# 140314_AriloTX_REV2_0_0.net
KiCad netlist of a schematic drawn in EAGLE
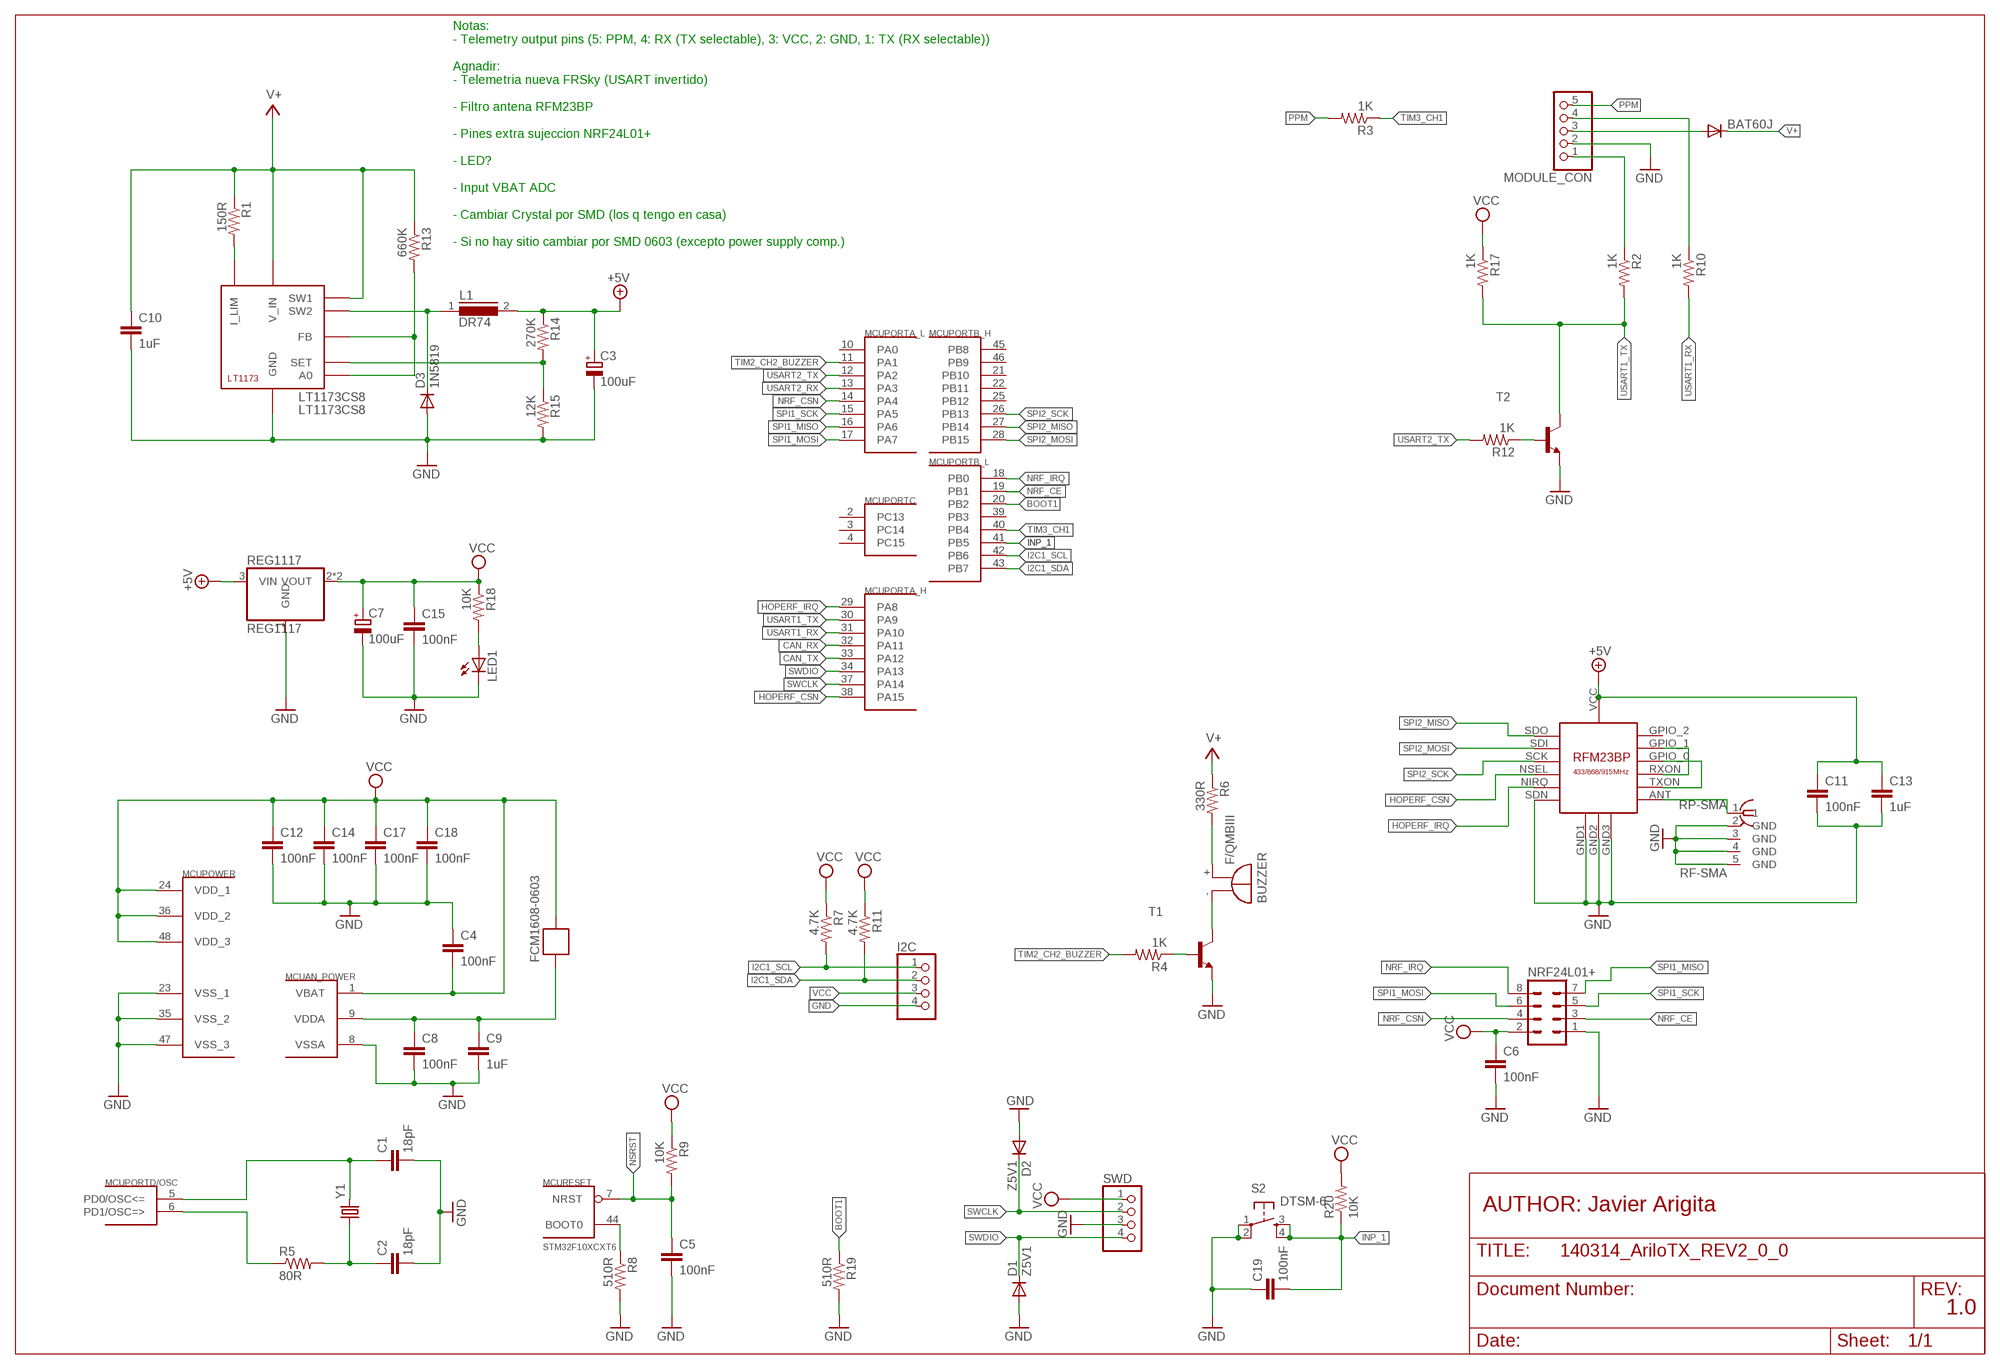
[diagram p0: schematic, sheet 1]

(export (version "E")
  (design (tool "Eeschema 10.0.6"))
  (components
    (comp (ref "BAT60J")
      (value "DIODE-SOD323-R")
      (footprint "eagle-import:SOD323-R")
      (libsource (lib "eagle-import") (part "DIODE-SOD323-R"))
    )
    (comp (ref "BUZZER")
      (value "F/QMBIII")
      (footprint "eagle-import:F_QMBIII")
      (libsource (lib "eagle-import") (part "F/QMBIII"))
    )
    (comp (ref "C1")
      (value "18pF")
      (footprint "eagle-import:C0805")
      (libsource (lib "eagle-import") (part "C-EUC0805"))
    )
    (comp (ref "C2")
      (value "18pF")
      (footprint "eagle-import:C0805")
      (libsource (lib "eagle-import") (part "C-EUC0805"))
    )
    (comp (ref "C3")
      (value "100uF")
      (footprint "eagle-import:SMC_B")
      (libsource (lib "eagle-import") (part "CPOL-EUSMCB"))
    )
    (comp (ref "C4")
      (value "100nF")
      (footprint "eagle-import:C0805")
      (libsource (lib "eagle-import") (part "C-EUC0805"))
    )
    (comp (ref "C5")
      (value "100nF")
      (footprint "eagle-import:C0805")
      (libsource (lib "eagle-import") (part "C-EUC0805"))
    )
    (comp (ref "C6")
      (value "100nF")
      (footprint "eagle-import:C0805")
      (libsource (lib "eagle-import") (part "C-EUC0805"))
    )
    (comp (ref "C7")
      (value "100uF")
      (footprint "eagle-import:SMC_B")
      (libsource (lib "eagle-import") (part "CPOL-EUSMCB"))
    )
    (comp (ref "C8")
      (value "100nF")
      (footprint "eagle-import:C0805")
      (libsource (lib "eagle-import") (part "C-EUC0805"))
    )
    (comp (ref "C9")
      (value "1uF")
      (footprint "eagle-import:C3216")
      (libsource (lib "eagle-import") (part "resistor_C-EUC3216"))
    )
    (comp (ref "C10")
      (value "1uF")
      (footprint "eagle-import:C3216")
      (libsource (lib "eagle-import") (part "resistor_C-EUC3216"))
    )
    (comp (ref "C11")
      (value "100nF")
      (footprint "eagle-import:C0805")
      (libsource (lib "eagle-import") (part "C-EUC0805"))
    )
    (comp (ref "C12")
      (value "100nF")
      (footprint "eagle-import:C0805")
      (libsource (lib "eagle-import") (part "C-EUC0805"))
    )
    (comp (ref "C13")
      (value "1uF")
      (footprint "eagle-import:C3216")
      (libsource (lib "eagle-import") (part "resistor_C-EUC3216"))
    )
    (comp (ref "C14")
      (value "100nF")
      (footprint "eagle-import:C0805")
      (libsource (lib "eagle-import") (part "C-EUC0805"))
    )
    (comp (ref "C15")
      (value "100nF")
      (footprint "eagle-import:C0805")
      (libsource (lib "eagle-import") (part "C-EUC0805"))
    )
    (comp (ref "C17")
      (value "100nF")
      (footprint "eagle-import:C0805")
      (libsource (lib "eagle-import") (part "C-EUC0805"))
    )
    (comp (ref "C18")
      (value "100nF")
      (footprint "eagle-import:C0805")
      (libsource (lib "eagle-import") (part "C-EUC0805"))
    )
    (comp (ref "C19")
      (value "100nF")
      (footprint "eagle-import:C0805")
      (libsource (lib "eagle-import") (part "C-EUC0805"))
    )
    (comp (ref "D1")
      (value "Z5V1")
      (footprint "eagle-import:SOD323-R")
      (libsource (lib "eagle-import") (part "DIODE-SOD323-R"))
    )
    (comp (ref "D2")
      (value "Z5V1")
      (footprint "eagle-import:SOD323-R")
      (libsource (lib "eagle-import") (part "DIODE-SOD323-R"))
    )
    (comp (ref "D3")
      (value "1N5819")
      (footprint "eagle-import:DO214AC")
      (libsource (lib "eagle-import") (part "DIODE-DO214AC"))
    )
    (comp (ref "FCM1608-0603")
      (value "FERRITE-BEAD")
      (footprint "eagle-import:R0603")
      (libsource (lib "eagle-import") (part "FERRITE-BEAD"))
    )
    (comp (ref "I2C")
      (value "PINHD-1X4")
      (footprint "eagle-import:1X04")
      (libsource (lib "eagle-import") (part "PINHD-1X4"))
    )
    (comp (ref "L1")
      (value "DR74")
      (footprint "eagle-import:DR74")
      (libsource (lib "eagle-import") (part "DR74"))
    )
    (comp (ref "LED1")
      (value "LED0805")
      (footprint "eagle-import:CHIPLED_0805")
      (libsource (lib "eagle-import") (part "LED0805"))
    )
    (comp (ref "LT1173CS8")
      (value "LT1173CS8")
      (footprint "eagle-import:SOIC8")
      (libsource (lib "eagle-import") (part "LT1173CS8"))
    )
    (comp (ref "MCU")
      (value "STM32F10XCXT6")
      (footprint "eagle-import:TQFP48")
      (libsource (lib "eagle-import") (part "STM32F10XCXT6"))
    )
    (comp (ref "MODULE_CON")
      (value "PINHD-1X5")
      (footprint "eagle-import:1X05")
      (libsource (lib "eagle-import") (part "PINHD-1X5"))
    )
    (comp (ref "NRF24L01+")
      (value "MA04-2")
      (footprint "eagle-import:MA04-2")
      (libsource (lib "eagle-import") (part "MA04-2"))
    )
    (comp (ref "R1")
      (value "150R")
      (footprint "eagle-import:R0805")
      (libsource (lib "eagle-import") (part "RESISTOR0805"))
    )
    (comp (ref "R2")
      (value "1K")
      (footprint "eagle-import:R0805")
      (libsource (lib "eagle-import") (part "RESISTOR0805"))
    )
    (comp (ref "R3")
      (value "1K")
      (footprint "eagle-import:R0805")
      (libsource (lib "eagle-import") (part "RESISTOR0805"))
    )
    (comp (ref "R4")
      (value "1K")
      (footprint "eagle-import:R0805")
      (libsource (lib "eagle-import") (part "RESISTOR0805"))
    )
    (comp (ref "R5")
      (value "80R")
      (footprint "eagle-import:R0805")
      (libsource (lib "eagle-import") (part "RESISTOR0805"))
    )
    (comp (ref "R6")
      (value "330R")
      (footprint "eagle-import:R0805")
      (libsource (lib "eagle-import") (part "RESISTOR0805"))
    )
    (comp (ref "R7")
      (value "4.7K")
      (footprint "eagle-import:R0805")
      (libsource (lib "eagle-import") (part "RESISTOR0805"))
    )
    (comp (ref "R8")
      (value "510R")
      (footprint "eagle-import:R0805")
      (libsource (lib "eagle-import") (part "RESISTOR0805"))
    )
    (comp (ref "R9")
      (value "10K")
      (footprint "eagle-import:R0805")
      (libsource (lib "eagle-import") (part "RESISTOR0805"))
    )
    (comp (ref "R10")
      (value "1K")
      (footprint "eagle-import:R0805")
      (libsource (lib "eagle-import") (part "RESISTOR0805"))
    )
    (comp (ref "R11")
      (value "4.7K")
      (footprint "eagle-import:R0805")
      (libsource (lib "eagle-import") (part "RESISTOR0805"))
    )
    (comp (ref "R12")
      (value "1K")
      (footprint "eagle-import:R0805")
      (libsource (lib "eagle-import") (part "RESISTOR0805"))
    )
    (comp (ref "R13")
      (value "660K")
      (footprint "eagle-import:R0805")
      (libsource (lib "eagle-import") (part "RESISTOR0805"))
    )
    (comp (ref "R14")
      (value "270K")
      (footprint "eagle-import:R0805")
      (libsource (lib "eagle-import") (part "RESISTOR0805"))
    )
    (comp (ref "R15")
      (value "12K")
      (footprint "eagle-import:R0805")
      (libsource (lib "eagle-import") (part "RESISTOR0805"))
    )
    (comp (ref "R17")
      (value "1K")
      (footprint "eagle-import:R0805")
      (libsource (lib "eagle-import") (part "RESISTOR0805"))
    )
    (comp (ref "R18")
      (value "10K")
      (footprint "eagle-import:R0805")
      (libsource (lib "eagle-import") (part "RESISTOR0805"))
    )
    (comp (ref "R19")
      (value "510R")
      (footprint "eagle-import:R0805")
      (libsource (lib "eagle-import") (part "RESISTOR0805"))
    )
    (comp (ref "R20")
      (value "10K")
      (footprint "eagle-import:R0805")
      (libsource (lib "eagle-import") (part "RESISTOR0805"))
    )
    (comp (ref "REG1117")
      (value "REG1117")
      (footprint "eagle-import:SOT223")
      (libsource (lib "eagle-import") (part "REG1117"))
    )
    (comp (ref "RP-SMA")
      (value "RF-SMA")
      (footprint "eagle-import:BU-SMA-H")
      (libsource (lib "eagle-import") (part "RF-SMA"))
    )
    (comp (ref "S2")
      (value "DTSM-6")
      (footprint "eagle-import:DTSM-6")
      (libsource (lib "eagle-import") (part "DTSM-6"))
    )
    (comp (ref "SWD")
      (value "PINHD-1X4")
      (footprint "eagle-import:1X04")
      (libsource (lib "eagle-import") (part "PINHD-1X4"))
    )
    (comp (ref "T1")
      (value "BC848-NPN-SOT23-BEC")
      (footprint "eagle-import:SOT23-BEC")
      (libsource (lib "eagle-import") (part "-NPN-SOT23-BECBC848"))
    )
    (comp (ref "T2")
      (value "BC848-NPN-SOT23-BEC")
      (footprint "eagle-import:SOT23-BEC")
      (libsource (lib "eagle-import") (part "-NPN-SOT23-BECBC848"))
    )
    (comp (ref "U$1")
      (value "RFM23BP")
      (footprint "eagle-import:RFM23BP")
      (libsource (lib "eagle-import") (part "RFM23BP"))
    )
    (comp (ref "Y1")
      (value "CRYSTAL5X3")
      (footprint "eagle-import:CRYSTAL-SMD-5X3")
      (libsource (lib "eagle-import") (part "CRYSTAL5X3"))
    )
  )
  (nets
    (net (code "1") (name "+5V") (class "Default")
      (node (ref "C11") (pin "1") (pinfunction "1_1") (pintype "passive"))
      (node (ref "C13") (pin "1") (pinfunction "1_1") (pintype "passive"))
      (node (ref "C3") (pin "+") (pinfunction "+_+") (pintype "passive"))
      (node (ref "L1") (pin "2") (pinfunction "2_2") (pintype "passive"))
      (node (ref "R14") (pin "1") (pinfunction "1_1") (pintype "passive"))
      (node (ref "REG1117") (pin "3") (pinfunction "VIN_3") (pintype "input"))
      (node (ref "U$1") (pin "VCC") (pinfunction "VCC_VCC") (pintype "power_in"))
    )
    (net (code "2") (name "BOOT1") (class "Default")
      (node (ref "MCU") (pin "20") (pinfunction "PB2_20") (pintype "bidirectional"))
      (node (ref "R19") (pin "1") (pinfunction "1_1") (pintype "passive"))
    )
    (net (code "3") (name "CAN_RX") (class "Default")
      (node (ref "MCU") (pin "32") (pinfunction "PA11_32") (pintype "bidirectional"))
    )
    (net (code "4") (name "CAN_TX") (class "Default")
      (node (ref "MCU") (pin "33") (pinfunction "PA12_33") (pintype "bidirectional"))
    )
    (net (code "5") (name "GND") (class "Default")
      (node (ref "C1") (pin "2") (pinfunction "2_2") (pintype "passive"))
      (node (ref "C10") (pin "2") (pinfunction "2_2") (pintype "passive"))
      (node (ref "C11") (pin "2") (pinfunction "2_2") (pintype "passive"))
      (node (ref "C12") (pin "2") (pinfunction "2_2") (pintype "passive"))
      (node (ref "C13") (pin "2") (pinfunction "2_2") (pintype "passive"))
      (node (ref "C14") (pin "2") (pinfunction "2_2") (pintype "passive"))
      (node (ref "C15") (pin "2") (pinfunction "2_2") (pintype "passive"))
      (node (ref "C17") (pin "2") (pinfunction "2_2") (pintype "passive"))
      (node (ref "C18") (pin "2") (pinfunction "2_2") (pintype "passive"))
      (node (ref "C19") (pin "1") (pinfunction "1_1") (pintype "passive"))
      (node (ref "C2") (pin "2") (pinfunction "2_2") (pintype "passive"))
      (node (ref "C3") (pin "-") (pinfunction "-_-") (pintype "passive"))
      (node (ref "C4") (pin "1") (pinfunction "1_1") (pintype "passive"))
      (node (ref "C5") (pin "2") (pinfunction "2_2") (pintype "passive"))
      (node (ref "C6") (pin "2") (pinfunction "2_2") (pintype "passive"))
      (node (ref "C7") (pin "-") (pinfunction "-_-") (pintype "passive"))
      (node (ref "C8") (pin "2") (pinfunction "2_2") (pintype "passive"))
      (node (ref "C9") (pin "2") (pinfunction "2_2") (pintype "passive"))
      (node (ref "D1") (pin "A") (pinfunction "A_A") (pintype "passive"))
      (node (ref "D2") (pin "A") (pinfunction "A_A") (pintype "passive"))
      (node (ref "D3") (pin "A") (pinfunction "A_A") (pintype "passive"))
      (node (ref "I2C") (pin "4") (pinfunction "4_4") (pintype "passive"))
      (node (ref "LED1") (pin "C") (pinfunction "C_C") (pintype "passive"))
      (node (ref "LT1173CS8") (pin "5") (pinfunction "GND_5") (pintype "power_in"))
      (node (ref "MCU") (pin "23") (pinfunction "VSS_1_23") (pintype "power_in"))
      (node (ref "MCU") (pin "35") (pinfunction "VSS_2_35") (pintype "power_in"))
      (node (ref "MCU") (pin "47") (pinfunction "VSS_3_47") (pintype "power_in"))
      (node (ref "MCU") (pin "8") (pinfunction "VSSA_8") (pintype "power_in"))
      (node (ref "MODULE_CON") (pin "2") (pinfunction "2_2") (pintype "passive"))
      (node (ref "NRF24L01+") (pin "1") (pinfunction "1_1") (pintype "passive"))
      (node (ref "R15") (pin "2") (pinfunction "2_2") (pintype "passive"))
      (node (ref "R19") (pin "2") (pinfunction "2_2") (pintype "passive"))
      (node (ref "R8") (pin "2") (pinfunction "2_2") (pintype "passive"))
      (node (ref "REG1117") (pin "1") (pinfunction "GND_1") (pintype "power_in"))
      (node (ref "RP-SMA") (pin "2") (pinfunction "GND_2") (pintype "power_in"))
      (node (ref "RP-SMA") (pin "3") (pinfunction "GND_3") (pintype "bidirectional"))
      (node (ref "RP-SMA") (pin "4") (pinfunction "GND_4") (pintype "bidirectional"))
      (node (ref "RP-SMA") (pin "5") (pinfunction "GND_5") (pintype "bidirectional"))
      (node (ref "S2") (pin "1") (pinfunction "1_1") (pintype "passive"))
      (node (ref "S2") (pin "2") (pinfunction "2_2") (pintype "passive"))
      (node (ref "SWD") (pin "3") (pinfunction "3_3") (pintype "passive"))
      (node (ref "T1") (pin "E") (pinfunction "E_E") (pintype "passive"))
      (node (ref "T2") (pin "E") (pinfunction "E_E") (pintype "passive"))
      (node (ref "U$1") (pin "GND1") (pinfunction "GND1_GND1") (pintype "power_in"))
      (node (ref "U$1") (pin "GND2") (pinfunction "GND2_GND2") (pintype "power_in"))
      (node (ref "U$1") (pin "GND3") (pinfunction "GND3_GND3") (pintype "power_in"))
      (node (ref "U$1") (pin "SDN") (pinfunction "SDN_SDN") (pintype "bidirectional"))
    )
    (net (code "6") (name "HOPERF_CSN") (class "Default")
      (node (ref "MCU") (pin "38") (pinfunction "PA15_38") (pintype "bidirectional"))
      (node (ref "U$1") (pin "NSEL") (pinfunction "NSEL_NSEL") (pintype "bidirectional"))
    )
    (net (code "7") (name "HOPERF_IRQ") (class "Default")
      (node (ref "MCU") (pin "29") (pinfunction "PA8_29") (pintype "bidirectional"))
      (node (ref "U$1") (pin "NIRQ") (pinfunction "NIRQ_NIRQ") (pintype "bidirectional"))
    )
    (net (code "8") (name "I2C1_SCL") (class "Default")
      (node (ref "I2C") (pin "1") (pinfunction "1_1") (pintype "passive"))
      (node (ref "MCU") (pin "42") (pinfunction "PB6_42") (pintype "bidirectional"))
      (node (ref "R7") (pin "2") (pinfunction "2_2") (pintype "passive"))
    )
    (net (code "9") (name "I2C1_SDA") (class "Default")
      (node (ref "I2C") (pin "2") (pinfunction "2_2") (pintype "passive"))
      (node (ref "MCU") (pin "43") (pinfunction "PB7_43") (pintype "bidirectional"))
      (node (ref "R11") (pin "2") (pinfunction "2_2") (pintype "passive"))
    )
    (net (code "10") (name "INP_1") (class "Default")
      (node (ref "C19") (pin "2") (pinfunction "2_2") (pintype "passive"))
      (node (ref "MCU") (pin "41") (pinfunction "PB5_41") (pintype "bidirectional"))
      (node (ref "R20") (pin "1") (pinfunction "1_1") (pintype "passive"))
      (node (ref "S2") (pin "3") (pinfunction "3_3") (pintype "passive"))
      (node (ref "S2") (pin "4") (pinfunction "4_4") (pintype "passive"))
    )
    (net (code "11") (name "NRF_CE") (class "Default")
      (node (ref "MCU") (pin "19") (pinfunction "PB1_19") (pintype "bidirectional"))
      (node (ref "NRF24L01+") (pin "3") (pinfunction "3_3") (pintype "passive"))
    )
    (net (code "12") (name "NRF_CSN") (class "Default")
      (node (ref "MCU") (pin "14") (pinfunction "PA4_14") (pintype "bidirectional"))
      (node (ref "NRF24L01+") (pin "4") (pinfunction "4_4") (pintype "passive"))
    )
    (net (code "13") (name "NRF_IRQ") (class "Default")
      (node (ref "MCU") (pin "18") (pinfunction "PB0_18") (pintype "bidirectional"))
      (node (ref "NRF24L01+") (pin "8") (pinfunction "8_8") (pintype "passive"))
    )
    (net (code "14") (name "NSRST") (class "Default")
      (node (ref "C5") (pin "1") (pinfunction "1_1") (pintype "passive"))
      (node (ref "MCU") (pin "7") (pinfunction "NRST_7") (pintype "input"))
      (node (ref "R9") (pin "2") (pinfunction "2_2") (pintype "passive"))
    )
    (net (code "15") (name "Net-(BAT60J-PadA)") (class "Default")
      (node (ref "BAT60J") (pin "A") (pinfunction "A_A") (pintype "passive"))
      (node (ref "MODULE_CON") (pin "3") (pinfunction "3_3") (pintype "passive"))
    )
    (net (code "16") (name "Net-(BUZZER-+)") (class "Default")
      (node (ref "BUZZER") (pin "-") (pinfunction "+_-") (pintype "passive"))
      (node (ref "T1") (pin "C") (pinfunction "C_C") (pintype "passive"))
    )
    (net (code "17") (name "Net-(BUZZER--)") (class "Default")
      (node (ref "BUZZER") (pin "+") (pinfunction "-_+") (pintype "passive"))
      (node (ref "R6") (pin "2") (pinfunction "2_2") (pintype "passive"))
    )
    (net (code "18") (name "Net-(C2-Pad1)") (class "Default")
      (node (ref "C2") (pin "1") (pinfunction "1_1") (pintype "passive"))
      (node (ref "R5") (pin "2") (pinfunction "2_2") (pintype "passive"))
      (node (ref "Y1") (pin "1") (pinfunction "1_1") (pintype "passive"))
    )
    (net (code "19") (name "Net-(FCM1608-0603-P$2)") (class "Default")
      (node (ref "C8") (pin "1") (pinfunction "1_1") (pintype "passive"))
      (node (ref "C9") (pin "1") (pinfunction "1_1") (pintype "passive"))
      (node (ref "FCM1608-0603") (pin "2") (pinfunction "P$2_2") (pintype "bidirectional"))
      (node (ref "MCU") (pin "9") (pinfunction "VDDA_9") (pintype "power_in"))
    )
    (net (code "20") (name "Net-(LED1-PadA)") (class "Default")
      (node (ref "LED1") (pin "A") (pinfunction "A_A") (pintype "passive"))
      (node (ref "R18") (pin "2") (pinfunction "2_2") (pintype "passive"))
    )
    (net (code "21") (name "Net-(LT1173CS8-A0)") (class "Default")
      (node (ref "LT1173CS8") (pin "6") (pinfunction "A0_6") (pintype "passive"))
      (node (ref "LT1173CS8") (pin "8") (pinfunction "FB_8") (pintype "passive"))
      (node (ref "R13") (pin "2") (pinfunction "2_2") (pintype "passive"))
    )
    (net (code "22") (name "Net-(LT1173CS8-I_LIM)") (class "Default")
      (node (ref "LT1173CS8") (pin "1") (pinfunction "I_LIM_1") (pintype "passive"))
      (node (ref "R1") (pin "2") (pinfunction "2_2") (pintype "passive"))
    )
    (net (code "23") (name "Net-(LT1173CS8-SET)") (class "Default")
      (node (ref "LT1173CS8") (pin "7") (pinfunction "SET_7") (pintype "passive"))
      (node (ref "R14") (pin "2") (pinfunction "2_2") (pintype "passive"))
      (node (ref "R15") (pin "1") (pinfunction "1_1") (pintype "passive"))
    )
    (net (code "24") (name "Net-(LT1173CS8-SW2)") (class "Default")
      (node (ref "D3") (pin "C") (pinfunction "C_C") (pintype "passive"))
      (node (ref "L1") (pin "1") (pinfunction "1_1") (pintype "passive"))
      (node (ref "LT1173CS8") (pin "4") (pinfunction "SW2_4") (pintype "passive"))
    )
    (net (code "25") (name "Net-(MCUG-PD0{slash}OSC<=)") (class "Default")
      (node (ref "C1") (pin "1") (pinfunction "1_1") (pintype "passive"))
      (node (ref "MCU") (pin "5") (pinfunction "PD0/OSC<=_5") (pintype "bidirectional"))
      (node (ref "Y1") (pin "3") (pinfunction "2_3") (pintype "passive"))
    )
    (net (code "26") (name "Net-(MCUG-PD1{slash}OSC=>)") (class "Default")
      (node (ref "MCU") (pin "6") (pinfunction "PD1/OSC=>_6") (pintype "bidirectional"))
      (node (ref "R5") (pin "1") (pinfunction "1_1") (pintype "passive"))
    )
    (net (code "27") (name "Net-(MCUI-BOOT0)") (class "Default")
      (node (ref "MCU") (pin "44") (pinfunction "BOOT0_44") (pintype "input"))
      (node (ref "R8") (pin "1") (pinfunction "1_1") (pintype "passive"))
    )
    (net (code "28") (name "Net-(MODULE_CON-Pad1)") (class "Default")
      (node (ref "MODULE_CON") (pin "1") (pinfunction "1_1") (pintype "passive"))
      (node (ref "R2") (pin "1") (pinfunction "1_1") (pintype "passive"))
    )
    (net (code "29") (name "Net-(MODULE_CON-Pad4)") (class "Default")
      (node (ref "MODULE_CON") (pin "4") (pinfunction "4_4") (pintype "passive"))
      (node (ref "R10") (pin "1") (pinfunction "1_1") (pintype "passive"))
    )
    (net (code "30") (name "Net-(R4-Pad1)") (class "Default")
      (node (ref "R4") (pin "1") (pinfunction "1_1") (pintype "passive"))
      (node (ref "T1") (pin "B") (pinfunction "B_B") (pintype "passive"))
    )
    (net (code "31") (name "Net-(R12-Pad1)") (class "Default")
      (node (ref "R12") (pin "1") (pinfunction "1_1") (pintype "passive"))
      (node (ref "T2") (pin "B") (pinfunction "B_B") (pintype "passive"))
    )
    (net (code "32") (name "Net-(RP-SMA-Pad1)") (class "Default")
      (node (ref "RP-SMA") (pin "1") (pinfunction "1_1") (pintype "passive"))
      (node (ref "U$1") (pin "ANT") (pinfunction "ANT_ANT") (pintype "bidirectional"))
    )
    (net (code "33") (name "Net-(U$1-PadGPIO_0)") (class "Default")
      (node (ref "U$1") (pin "GPIO_0") (pinfunction "GPIO_0_GPIO_0") (pintype "bidirectional"))
      (node (ref "U$1") (pin "TXON") (pinfunction "TXON_TXON") (pintype "bidirectional"))
    )
    (net (code "34") (name "Net-(U$1-PadGPIO_1)") (class "Default")
      (node (ref "U$1") (pin "GPIO_1") (pinfunction "GPIO_1_GPIO_1") (pintype "bidirectional"))
      (node (ref "U$1") (pin "RXON") (pinfunction "RXON_RXON") (pintype "bidirectional"))
    )
    (net (code "35") (name "PPM") (class "Default")
      (node (ref "MODULE_CON") (pin "5") (pinfunction "5_5") (pintype "passive"))
      (node (ref "R3") (pin "2") (pinfunction "2_2") (pintype "passive"))
    )
    (net (code "36") (name "SPI1_MISO") (class "Default")
      (node (ref "MCU") (pin "16") (pinfunction "PA6_16") (pintype "bidirectional"))
      (node (ref "NRF24L01+") (pin "7") (pinfunction "7_7") (pintype "passive"))
    )
    (net (code "37") (name "SPI1_MOSI") (class "Default")
      (node (ref "MCU") (pin "17") (pinfunction "PA7_17") (pintype "bidirectional"))
      (node (ref "NRF24L01+") (pin "6") (pinfunction "6_6") (pintype "passive"))
    )
    (net (code "38") (name "SPI1_SCK") (class "Default")
      (node (ref "MCU") (pin "15") (pinfunction "PA5_15") (pintype "bidirectional"))
      (node (ref "NRF24L01+") (pin "5") (pinfunction "5_5") (pintype "passive"))
    )
    (net (code "39") (name "SPI2_MISO") (class "Default")
      (node (ref "MCU") (pin "27") (pinfunction "PB14_27") (pintype "bidirectional"))
      (node (ref "U$1") (pin "SDO") (pinfunction "SDO_SDO") (pintype "bidirectional"))
    )
    (net (code "40") (name "SPI2_MOSI") (class "Default")
      (node (ref "MCU") (pin "28") (pinfunction "PB15_28") (pintype "bidirectional"))
      (node (ref "U$1") (pin "SDI") (pinfunction "SDI_SDI") (pintype "bidirectional"))
    )
    (net (code "41") (name "SPI2_SCK") (class "Default")
      (node (ref "MCU") (pin "26") (pinfunction "PB13_26") (pintype "bidirectional"))
      (node (ref "U$1") (pin "SCK") (pinfunction "SCK_SCK") (pintype "bidirectional"))
    )
    (net (code "42") (name "SWCLK") (class "Default")
      (node (ref "D2") (pin "C") (pinfunction "C_C") (pintype "passive"))
      (node (ref "MCU") (pin "37") (pinfunction "PA14_37") (pintype "bidirectional"))
      (node (ref "SWD") (pin "2") (pinfunction "2_2") (pintype "passive"))
    )
    (net (code "43") (name "SWDIO") (class "Default")
      (node (ref "D1") (pin "C") (pinfunction "C_C") (pintype "passive"))
      (node (ref "MCU") (pin "34") (pinfunction "PA13_34") (pintype "bidirectional"))
      (node (ref "SWD") (pin "4") (pinfunction "4_4") (pintype "passive"))
    )
    (net (code "44") (name "TIM2_CH2_BUZZER") (class "Default")
      (node (ref "MCU") (pin "11") (pinfunction "PA1_11") (pintype "bidirectional"))
      (node (ref "R4") (pin "2") (pinfunction "2_2") (pintype "passive"))
    )
    (net (code "45") (name "TIM3_CH1") (class "Default")
      (node (ref "MCU") (pin "40") (pinfunction "PB4_40") (pintype "bidirectional"))
      (node (ref "R3") (pin "1") (pinfunction "1_1") (pintype "passive"))
    )
    (net (code "46") (name "USART1_RX") (class "Default")
      (node (ref "MCU") (pin "31") (pinfunction "PA10_31") (pintype "bidirectional"))
      (node (ref "R10") (pin "2") (pinfunction "2_2") (pintype "passive"))
    )
    (net (code "47") (name "USART1_TX") (class "Default")
      (node (ref "MCU") (pin "30") (pinfunction "PA9_30") (pintype "bidirectional"))
      (node (ref "R17") (pin "2") (pinfunction "2_2") (pintype "passive"))
      (node (ref "R2") (pin "2") (pinfunction "2_2") (pintype "passive"))
      (node (ref "T2") (pin "C") (pinfunction "C_C") (pintype "passive"))
    )
    (net (code "48") (name "USART2_RX") (class "Default")
      (node (ref "MCU") (pin "13") (pinfunction "PA3_13") (pintype "bidirectional"))
    )
    (net (code "49") (name "USART2_TX") (class "Default")
      (node (ref "MCU") (pin "12") (pinfunction "PA2_12") (pintype "bidirectional"))
      (node (ref "R12") (pin "2") (pinfunction "2_2") (pintype "passive"))
    )
    (net (code "50") (name "V+") (class "Default")
      (node (ref "BAT60J") (pin "C") (pinfunction "C_C") (pintype "passive"))
      (node (ref "C10") (pin "1") (pinfunction "1_1") (pintype "passive"))
      (node (ref "LT1173CS8") (pin "2") (pinfunction "V_IN_2") (pintype "passive"))
      (node (ref "LT1173CS8") (pin "3") (pinfunction "SW1_3") (pintype "passive"))
      (node (ref "R1") (pin "1") (pinfunction "1_1") (pintype "passive"))
      (node (ref "R13") (pin "1") (pinfunction "1_1") (pintype "passive"))
      (node (ref "R6") (pin "1") (pinfunction "1_1") (pintype "passive"))
    )
    (net (code "51") (name "VCC") (class "Default")
      (node (ref "C12") (pin "1") (pinfunction "1_1") (pintype "passive"))
      (node (ref "C14") (pin "1") (pinfunction "1_1") (pintype "passive"))
      (node (ref "C15") (pin "1") (pinfunction "1_1") (pintype "passive"))
      (node (ref "C17") (pin "1") (pinfunction "1_1") (pintype "passive"))
      (node (ref "C18") (pin "1") (pinfunction "1_1") (pintype "passive"))
      (node (ref "C4") (pin "2") (pinfunction "2_2") (pintype "passive"))
      (node (ref "C6") (pin "1") (pinfunction "1_1") (pintype "passive"))
      (node (ref "C7") (pin "+") (pinfunction "+_+") (pintype "passive"))
      (node (ref "FCM1608-0603") (pin "1") (pinfunction "P$1_1") (pintype "bidirectional"))
      (node (ref "I2C") (pin "3") (pinfunction "3_3") (pintype "passive"))
      (node (ref "MCU") (pin "1") (pinfunction "VBAT_1") (pintype "power_in"))
      (node (ref "MCU") (pin "24") (pinfunction "VDD_1_24") (pintype "power_in"))
      (node (ref "MCU") (pin "36") (pinfunction "VDD_2_36") (pintype "power_in"))
      (node (ref "MCU") (pin "48") (pinfunction "VDD_3_48") (pintype "power_in"))
      (node (ref "NRF24L01+") (pin "2") (pinfunction "2_2") (pintype "passive"))
      (node (ref "R11") (pin "1") (pinfunction "1_1") (pintype "passive"))
      (node (ref "R17") (pin "1") (pinfunction "1_1") (pintype "passive"))
      (node (ref "R18") (pin "1") (pinfunction "1_1") (pintype "passive"))
      (node (ref "R20") (pin "2") (pinfunction "2_2") (pintype "passive"))
      (node (ref "R7") (pin "1") (pinfunction "1_1") (pintype "passive"))
      (node (ref "R9") (pin "1") (pinfunction "1_1") (pintype "passive"))
      (node (ref "REG1117") (pin "2") (pinfunction "VOUT_2") (pintype "power_in"))
      (node (ref "REG1117") (pin "4") (pinfunction "VOUT_4") (pintype "power_in"))
      (node (ref "SWD") (pin "1") (pinfunction "1_1") (pintype "passive"))
    )
    (net (code "52") (name "unconnected-(MCUC-PA0-Pad10)") (class "Default")
      (node (ref "MCU") (pin "10") (pinfunction "PA0_10") (pintype "bidirectional"))
    )
    (net (code "53") (name "unconnected-(MCUD-PB8-Pad45)") (class "Default")
      (node (ref "MCU") (pin "45") (pinfunction "PB8_45") (pintype "bidirectional"))
    )
    (net (code "54") (name "unconnected-(MCUD-PB9-Pad46)") (class "Default")
      (node (ref "MCU") (pin "46") (pinfunction "PB9_46") (pintype "bidirectional"))
    )
    (net (code "55") (name "unconnected-(MCUD-PB10-Pad21)") (class "Default")
      (node (ref "MCU") (pin "21") (pinfunction "PB10_21") (pintype "bidirectional"))
    )
    (net (code "56") (name "unconnected-(MCUD-PB11-Pad22)") (class "Default")
      (node (ref "MCU") (pin "22") (pinfunction "PB11_22") (pintype "bidirectional"))
    )
    (net (code "57") (name "unconnected-(MCUD-PB12-Pad25)") (class "Default")
      (node (ref "MCU") (pin "25") (pinfunction "PB12_25") (pintype "bidirectional"))
    )
    (net (code "58") (name "unconnected-(MCUE-PB3-Pad39)") (class "Default")
      (node (ref "MCU") (pin "39") (pinfunction "PB3_39") (pintype "bidirectional"))
    )
    (net (code "59") (name "unconnected-(MCUF-PC13-Pad2)") (class "Default")
      (node (ref "MCU") (pin "2") (pinfunction "PC13_2") (pintype "bidirectional"))
    )
    (net (code "60") (name "unconnected-(MCUF-PC14-Pad3)") (class "Default")
      (node (ref "MCU") (pin "3") (pinfunction "PC14_3") (pintype "bidirectional"))
    )
    (net (code "61") (name "unconnected-(MCUF-PC15-Pad4)") (class "Default")
      (node (ref "MCU") (pin "4") (pinfunction "PC15_4") (pintype "bidirectional"))
    )
    (net (code "62") (name "unconnected-(U$1-PadGPIO_2)") (class "Default")
      (node (ref "U$1") (pin "GPIO_2") (pinfunction "GPIO_2_GPIO_2") (pintype "bidirectional"))
    )
  )
)
